# ELRS_Logic.net
KiCad netlist of a schematic drawn in Altium Designer
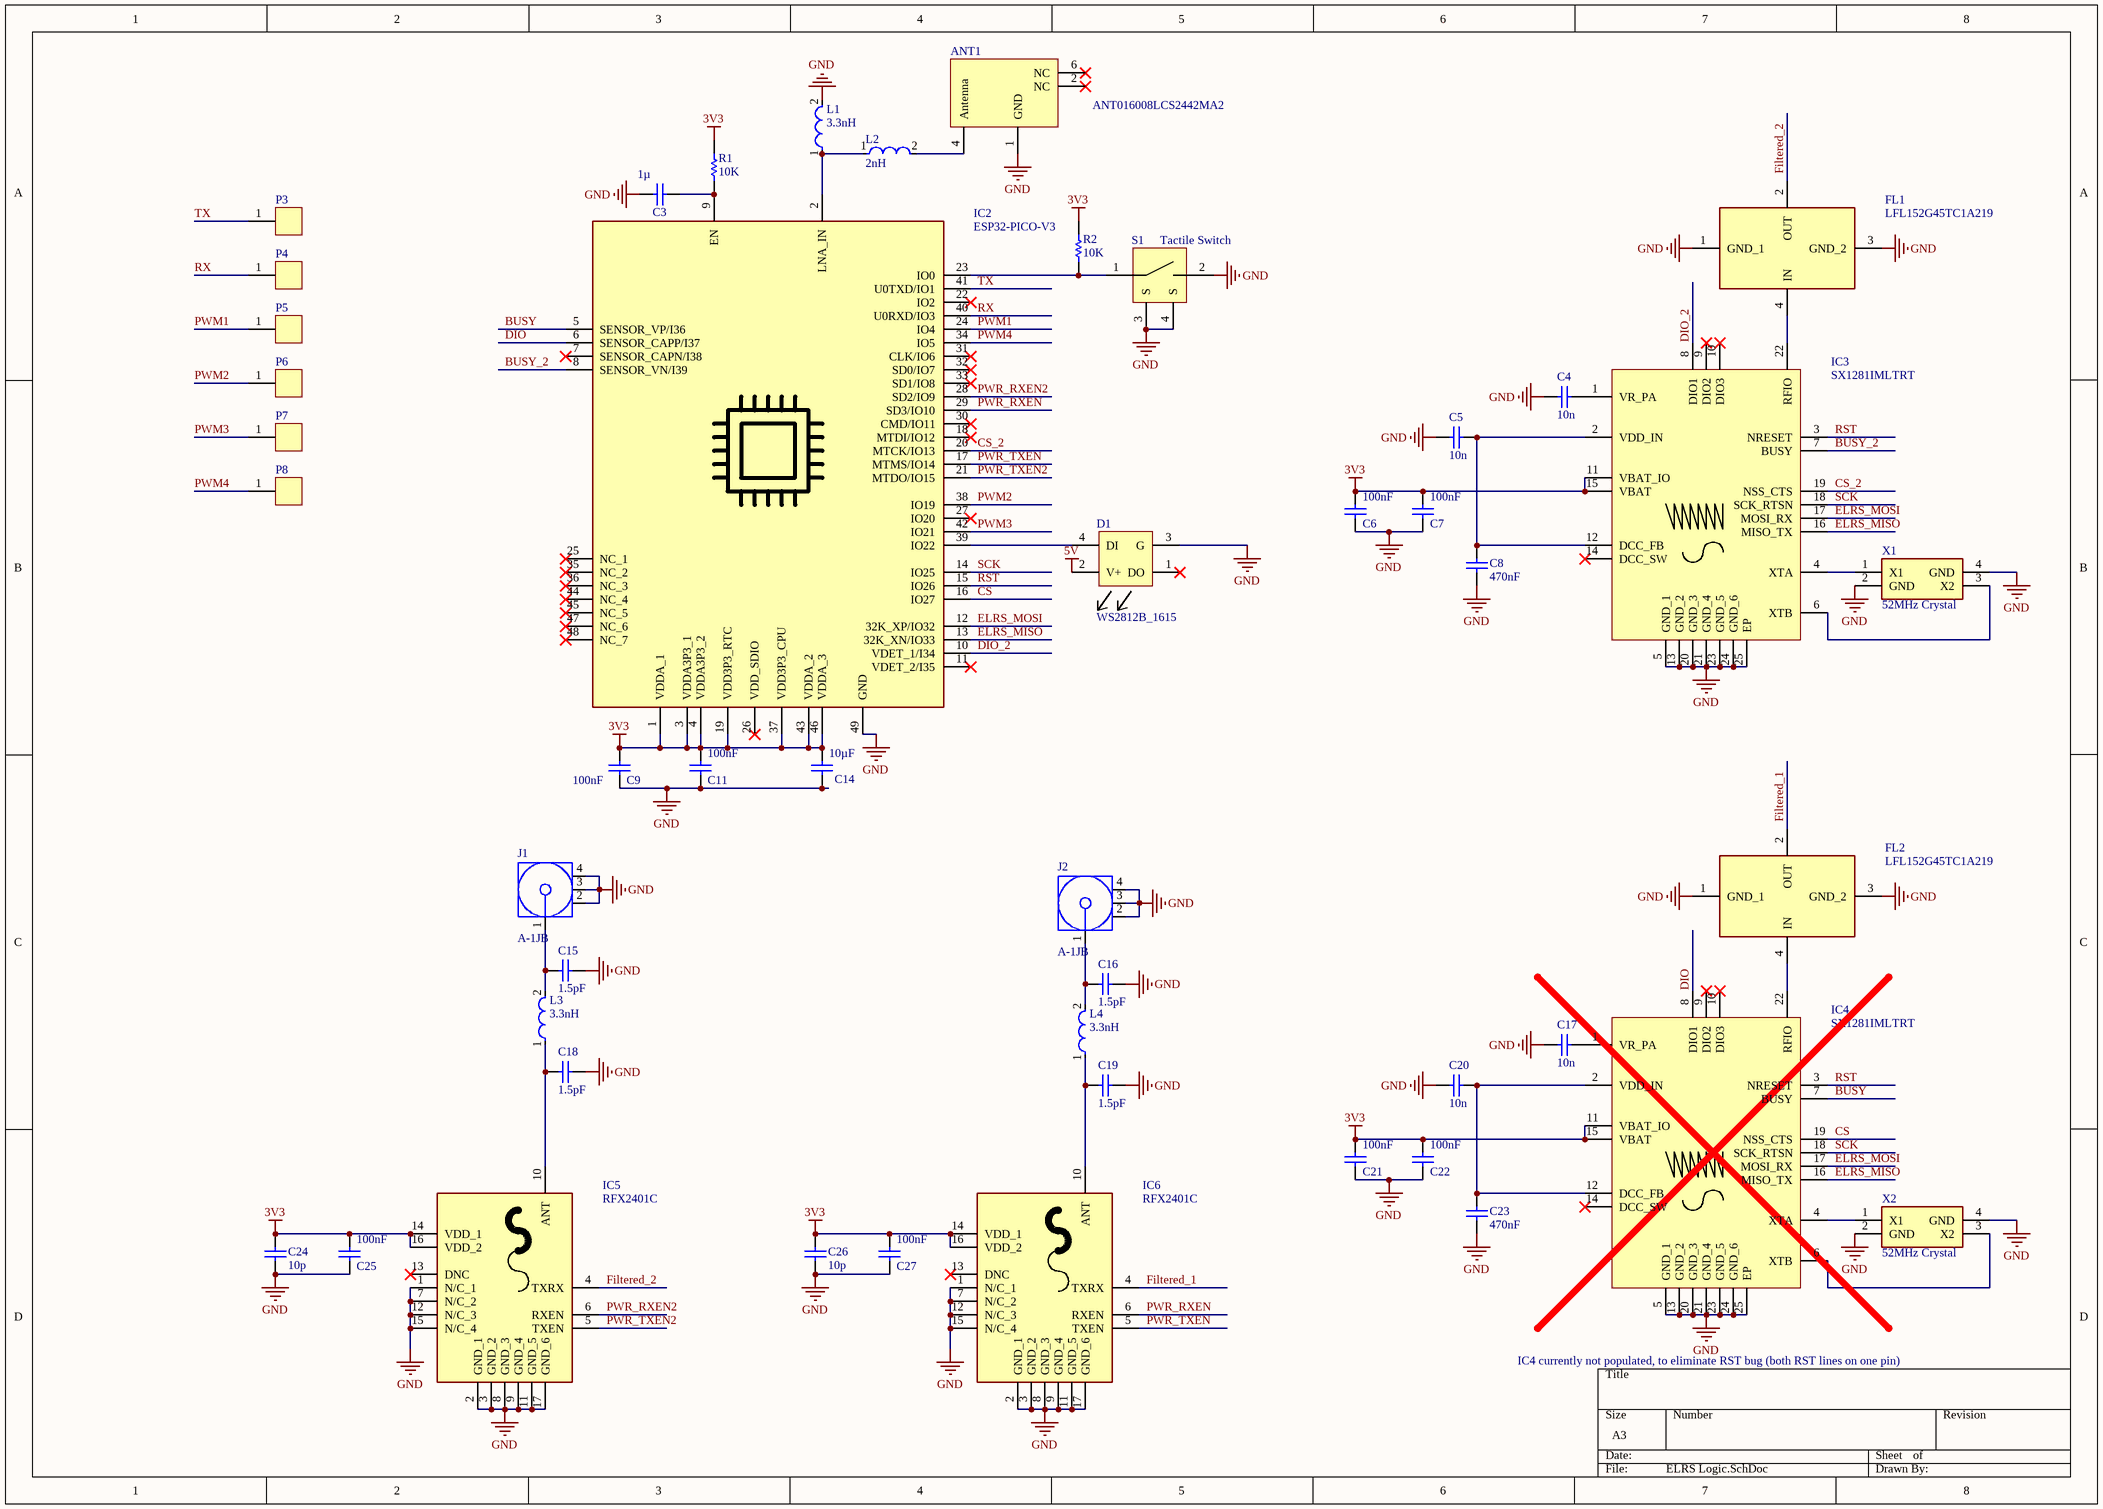
[diagram p0: ELRS Logic.SchDoc]

(export (version "E")
  (design (tool "Eeschema 10.0.6"))
  (components
    (comp (ref "ANT1")
      (value "ANT016008LCS2442MA2")
      (footprint "Custom Components:ANT016008LCS2442MA2")
      (description "Antenna")
      (fields (field (name "MOUSER PART NUMBER") "810-ANT168LCS2442MA2"))
      (libsource (lib "Custom Components") (part "ANT016008LCS2442MA2"))
    )
    (comp (ref "C3")
      (value "1µ")
      (footprint "WCAP-CSGP_0603_L1.6W0.8H0.8_Reflow")
      (description "WCAP-CSGP Multilayer Ceramic Chip Capacitor, General Purpose, size 0603, X7R, 100nF, 50VDC")
      (fields
        (field (name "MANUFACTURER PART NUMBER") "885012206095")
        (field (name "MANUFACTURER") "Wurth Elektronik")
      )
      (libsource (lib "Altium_WCAP-CSGP (rev22f)") (part "885012206095"))
    )
    (comp (ref "C4")
      (value "10n")
      (footprint "CAPC0603(1608)55_N")
      (description "Keramikvielschichtkondensator, SMD, Baureihe MC, ± 20%")
      (fields (field (name "MANUFACTURER") "Multicomp"))
      (libsource (lib "Standardbauteile") (part "Cap 10n"))
    )
    (comp (ref "C5")
      (value "10n")
      (footprint "CAPC0603(1608)55_N")
      (description "Keramikvielschichtkondensator, SMD, Baureihe MC, ± 20%")
      (fields (field (name "MANUFACTURER") "Multicomp"))
      (libsource (lib "Standardbauteile") (part "Cap 10n"))
    )
    (comp (ref "C6")
      (value "100nF")
      (footprint "WCAP-CSGP_0603_L1.6W0.8H0.8_Reflow")
      (description "WCAP-CSGP Multilayer Ceramic Chip Capacitor, General Purpose, size 0603, X7R, 100nF, 50VDC")
      (fields
        (field (name "MANUFACTURER PART NUMBER") "885012206095")
        (field (name "MANUFACTURER") "Wurth Elektronik")
      )
      (libsource (lib "Altium_WCAP-CSGP (rev22f)") (part "885012206095"))
    )
    (comp (ref "C7")
      (value "100nF")
      (footprint "WCAP-CSGP_0603_L1.6W0.8H0.8_Reflow")
      (description "WCAP-CSGP Multilayer Ceramic Chip Capacitor, General Purpose, size 0603, X7R, 100nF, 50VDC")
      (fields
        (field (name "MANUFACTURER PART NUMBER") "885012206095")
        (field (name "MANUFACTURER") "Wurth Elektronik")
      )
      (libsource (lib "Altium_WCAP-CSGP (rev22f)") (part "885012206095"))
    )
    (comp (ref "C8")
      (value "470nF")
      (footprint "0402 cap")
      (libsource (lib "Custom Components") (part "Capacitor 0402 100nF"))
    )
    (comp (ref "C9")
      (value "100nF")
      (footprint "WCAP-CSGP_0603_L1.6W0.8H0.8_Reflow")
      (description "WCAP-CSGP Multilayer Ceramic Chip Capacitor, General Purpose, size 0603, X7R, 100nF, 50VDC")
      (fields
        (field (name "MANUFACTURER PART NUMBER") "885012206095")
        (field (name "MANUFACTURER") "Wurth Elektronik")
      )
      (libsource (lib "Altium_WCAP-CSGP (rev22f)") (part "885012206095"))
    )
    (comp (ref "C11")
      (value "100nF")
      (footprint "WCAP-CSGP_0603_L1.6W0.8H0.8_Reflow")
      (description "WCAP-CSGP Multilayer Ceramic Chip Capacitor, General Purpose, size 0603, X7R, 100nF, 50VDC")
      (fields
        (field (name "MANUFACTURER PART NUMBER") "885012206095")
        (field (name "MANUFACTURER") "Wurth Elektronik")
      )
      (libsource (lib "Altium_WCAP-CSGP (rev22f)") (part "885012206095"))
    )
    (comp (ref "C14")
      (value "10µF")
      (footprint "WCAP-CSGP_0603_L1.6W0.8H0.8_Reflow")
      (description "WCAP-CSGP Multilayer Ceramic Chip Capacitor, General Purpose, size 0603, X5R, 10µF, 25VDC")
      (fields
        (field (name "MANUFACTURER PART NUMBER") "885012106031")
        (field (name "MANUFACTURER") "Wurth Elektronik")
      )
      (libsource (lib "Altium_WCAP-CSGP (rev22f)") (part "885012106031"))
    )
    (comp (ref "C15")
      (value "1.5pF")
      (footprint "0402 cap")
      (description "CL05C1R5BB5NNNC")
      (libsource (lib "Custom Components") (part "Capacitor 0402 100nF"))
    )
    (comp (ref "C16")
      (value "1.5pF")
      (footprint "0402 cap")
      (description "CL05C1R5BB5NNNC")
      (libsource (lib "Custom Components") (part "Capacitor 0402 100nF"))
    )
    (comp (ref "C17")
      (value "10n")
      (footprint "CAPC0603(1608)55_N")
      (description "Keramikvielschichtkondensator, SMD, Baureihe MC, ± 20%")
      (fields (field (name "MANUFACTURER") "Multicomp"))
      (libsource (lib "Standardbauteile") (part "Cap 10n"))
    )
    (comp (ref "C18")
      (value "1.5pF")
      (footprint "0402 cap")
      (description "CL05C1R5BB5NNNC")
      (libsource (lib "Custom Components") (part "Capacitor 0402 100nF"))
    )
    (comp (ref "C19")
      (value "1.5pF")
      (footprint "0402 cap")
      (description "CL05C1R5BB5NNNC")
      (libsource (lib "Custom Components") (part "Capacitor 0402 100nF"))
    )
    (comp (ref "C20")
      (value "10n")
      (footprint "CAPC0603(1608)55_N")
      (description "Keramikvielschichtkondensator, SMD, Baureihe MC, ± 20%")
      (fields (field (name "MANUFACTURER") "Multicomp"))
      (libsource (lib "Standardbauteile") (part "Cap 10n"))
    )
    (comp (ref "C21")
      (value "100nF")
      (footprint "WCAP-CSGP_0603_L1.6W0.8H0.8_Reflow")
      (description "WCAP-CSGP Multilayer Ceramic Chip Capacitor, General Purpose, size 0603, X7R, 100nF, 50VDC")
      (fields
        (field (name "MANUFACTURER PART NUMBER") "885012206095")
        (field (name "MANUFACTURER") "Wurth Elektronik")
      )
      (libsource (lib "Altium_WCAP-CSGP (rev22f)") (part "885012206095"))
    )
    (comp (ref "C22")
      (value "100nF")
      (footprint "WCAP-CSGP_0603_L1.6W0.8H0.8_Reflow")
      (description "WCAP-CSGP Multilayer Ceramic Chip Capacitor, General Purpose, size 0603, X7R, 100nF, 50VDC")
      (fields
        (field (name "MANUFACTURER PART NUMBER") "885012206095")
        (field (name "MANUFACTURER") "Wurth Elektronik")
      )
      (libsource (lib "Altium_WCAP-CSGP (rev22f)") (part "885012206095"))
    )
    (comp (ref "C23")
      (value "470nF")
      (footprint "0402 cap")
      (libsource (lib "Custom Components") (part "Capacitor 0402 100nF"))
    )
    (comp (ref "C24")
      (value "10p")
      (footprint "0402 cap")
      (libsource (lib "Custom Components") (part "Capacitor 0402 100nF"))
    )
    (comp (ref "C25")
      (value "100nF")
      (footprint "WCAP-CSGP_0603_L1.6W0.8H0.8_Reflow")
      (description "WCAP-CSGP Multilayer Ceramic Chip Capacitor, General Purpose, size 0603, X7R, 100nF, 50VDC")
      (fields
        (field (name "MANUFACTURER PART NUMBER") "885012206095")
        (field (name "MANUFACTURER") "Wurth Elektronik")
      )
      (libsource (lib "Altium_WCAP-CSGP (rev22f)") (part "885012206095"))
    )
    (comp (ref "C26")
      (value "10p")
      (footprint "0402 cap")
      (libsource (lib "Custom Components") (part "Capacitor 0402 100nF"))
    )
    (comp (ref "C27")
      (value "100nF")
      (footprint "WCAP-CSGP_0603_L1.6W0.8H0.8_Reflow")
      (description "WCAP-CSGP Multilayer Ceramic Chip Capacitor, General Purpose, size 0603, X7R, 100nF, 50VDC")
      (fields
        (field (name "MANUFACTURER PART NUMBER") "885012206095")
        (field (name "MANUFACTURER") "Wurth Elektronik")
      )
      (libsource (lib "Altium_WCAP-CSGP (rev22f)") (part "885012206095"))
    )
    (comp (ref "D1")
      (value "WS2812B_1615")
      (footprint "WS2812B_1615")
      (description "XINGLIGHT XL-1615RGBC-WS2812B")
      (libsource (lib "Custom Components") (part "WS2812B_1615"))
    )
    (comp (ref "FL1")
      (value "LFL152G45TC1A219")
      (footprint "LFL152G45TC1A219")
      (description "Filter")
      (fields (field (name "MOUSER PART NUMBER") "81-LFL152G45TC1A219"))
      (libsource (lib "Custom Components") (part "LFL152G45TC1A219"))
    )
    (comp (ref "FL2")
      (value "LFL152G45TC1A219")
      (footprint "LFL152G45TC1A219")
      (description "Filter")
      (fields (field (name "MOUSER PART NUMBER") "81-LFL152G45TC1A219"))
      (libsource (lib "Custom Components") (part "LFL152G45TC1A219"))
    )
    (comp (ref "IC2")
      (value "ESP32-PICO-V3")
      (footprint "Custom Components:ESP32PICOV3")
      (description "Integrated Circuit")
      (fields (field (name "MOUSER PART NUMBER") "356-ESP32-PICO-V3"))
      (libsource (lib "Custom Components") (part "ESP32-PICO-V3"))
    )
    (comp (ref "IC3")
      (value "SX1281IMLTRT")
      (footprint "Custom Components:QFN50P400X400X100-25N-D")
      (description "Integrated Circuit")
      (fields (field (name "MOUSER PART NUMBER") "947-SX1281IMLTRT"))
      (libsource (lib "Custom Components") (part "SX1281IMLTRT"))
    )
    (comp (ref "IC4")
      (value "SX1281IMLTRT")
      (footprint "Custom Components:QFN50P400X400X100-25N-D")
      (description "Integrated Circuit")
      (fields (field (name "MOUSER PART NUMBER") "947-SX1281IMLTRT"))
      (libsource (lib "Custom Components") (part "SX1281IMLTRT"))
    )
    (comp (ref "IC5")
      (value "RFX2401C")
      (footprint "Custom Components:QFN50P300X300X60-17N-D")
      (description "Integrated Circuit")
      (fields (field (name "MOUSER PART NUMBER") "477-RFX2401C"))
      (libsource (lib "Custom Components") (part "RFX2401C"))
    )
    (comp (ref "IC6")
      (value "RFX2401C")
      (footprint "Custom Components:QFN50P300X300X60-17N-D")
      (description "Integrated Circuit")
      (fields (field (name "MOUSER PART NUMBER") "477-RFX2401C"))
      (libsource (lib "Custom Components") (part "RFX2401C"))
    )
    (comp (ref "J1")
      (value "A-1JB")
      (footprint "AMPH-A-1JB_V")
      (description "AMC PCB Jack, 0 to 60 GHz, 60 V, -40 to 90 degC, 4-Pin SMD, RoHS, Tape and Reel")
      (fields (field (name "TOLERANCE") "10%"))
      (libsource (lib "Altium Content Vault") (part "CN-S-3F-RF4"))
    )
    (comp (ref "J2")
      (value "A-1JB")
      (footprint "AMPH-A-1JB_V")
      (description "AMC PCB Jack, 0 to 60 GHz, 60 V, -40 to 90 degC, 4-Pin SMD, RoHS, Tape and Reel")
      (fields (field (name "TOLERANCE") "10%"))
      (libsource (lib "Altium Content Vault") (part "CN-S-3F-RF4"))
    )
    (comp (ref "L1")
      (value "3.3nH")
      (footprint "FP-LQW15AN_00-W0_6-0_1-MFG")
      (description "MLG1005S3N3BT000")
      (libsource (lib "Altium Content Vault") (part "725321dda6339637d4d059423bc1c3c"))
    )
    (comp (ref "L2")
      (value "2nH")
      (footprint "FP-LQW15AN_00-W0_6-0_1-MFG")
      (description "MLG1005S3N3BT000")
      (libsource (lib "Altium Content Vault") (part "725321dda6339637d4d059423bc1c3c"))
    )
    (comp (ref "L3")
      (value "3.3nH")
      (footprint "FP-LQW15AN_00-W0_6-0_1-MFG")
      (description "MLG1005S3N3BT000")
      (libsource (lib "Altium Content Vault") (part "725321dda6339637d4d059423bc1c3c"))
    )
    (comp (ref "L4")
      (value "3.3nH")
      (footprint "FP-LQW15AN_00-W0_6-0_1-MFG")
      (description "MLG1005S3N3BT000")
      (libsource (lib "Altium Content Vault") (part "725321dda6339637d4d059423bc1c3c"))
    )
    (comp (ref "P3")
      (value "solder pad rounded single sided")
      (footprint "solder pad single sided rounded")
      (libsource (lib "Custom Components") (part "solder pad rounded single sided"))
    )
    (comp (ref "P4")
      (value "solder pad rounded single sided")
      (footprint "solder pad single sided rounded")
      (libsource (lib "Custom Components") (part "solder pad rounded single sided"))
    )
    (comp (ref "P5")
      (value "solder pad rounded single sided")
      (footprint "solder pad single sided rounded")
      (libsource (lib "Custom Components") (part "solder pad rounded single sided"))
    )
    (comp (ref "P6")
      (value "solder pad rounded single sided")
      (footprint "solder pad single sided rounded")
      (libsource (lib "Custom Components") (part "solder pad rounded single sided"))
    )
    (comp (ref "P7")
      (value "solder pad rounded single sided")
      (footprint "solder pad single sided rounded")
      (libsource (lib "Custom Components") (part "solder pad rounded single sided"))
    )
    (comp (ref "P8")
      (value "solder pad rounded single sided")
      (footprint "solder pad single sided rounded")
      (libsource (lib "Custom Components") (part "solder pad rounded single sided"))
    )
    (comp (ref "R1")
      (value "10K")
      (footprint "RESC0603(1608)_N")
      (description "Chipwiderstand, SMD, Baureihe MC, 1%")
      (fields (field (name "MANUFACTURER") "Multicomp"))
      (libsource (lib "Standardbauteile") (part "Res 1K"))
    )
    (comp (ref "R2")
      (value "10K")
      (footprint "RESC0603(1608)_N")
      (description "Chipwiderstand, SMD, Baureihe MC, 1%")
      (fields (field (name "MANUFACTURER") "Multicomp"))
      (libsource (lib "Standardbauteile") (part "Res 10K"))
    )
    (comp (ref "S1")
      (value "Tactile Switch")
      (footprint "Tactile Switch")
      (libsource (lib "Custom Components") (part "Tactile Switch"))
    )
    (comp (ref "X1")
      (value "52MHz Crystal")
      (footprint "2016 Crystal")
      (description "HCI XC21M4-52.000-F10NNHPL")
      (libsource (lib "Custom Components") (part "HCI XC21M4-52.000"))
    )
    (comp (ref "X2")
      (value "52MHz Crystal")
      (footprint "2016 Crystal")
      (description "HCI XC21M4-52.000-F10NNHPL")
      (libsource (lib "Custom Components") (part "HCI XC21M4-52.000"))
    )
  )
  (nets
    (net (code "1") (name "/BUSY") (class "Default")
      (node (ref "IC2") (pin "5") (pinfunction "SENSOR_VP/I36_5") (pintype "passive"))
      (node (ref "IC4") (pin "7") (pinfunction "BUSY_7") (pintype "passive"))
    )
    (net (code "2") (name "/BUSY_2") (class "Default")
      (node (ref "IC2") (pin "8") (pinfunction "SENSOR_VN/I39_8") (pintype "passive"))
      (node (ref "IC3") (pin "7") (pinfunction "BUSY_7") (pintype "passive"))
    )
    (net (code "3") (name "/CS") (class "Default")
      (node (ref "IC2") (pin "16") (pinfunction "IO27_16") (pintype "passive"))
      (node (ref "IC4") (pin "19") (pinfunction "NSS_CTS_19") (pintype "passive"))
    )
    (net (code "4") (name "/CS_2") (class "Default")
      (node (ref "IC2") (pin "20") (pinfunction "MTCK/IO13_20") (pintype "passive"))
      (node (ref "IC3") (pin "19") (pinfunction "NSS_CTS_19") (pintype "passive"))
    )
    (net (code "5") (name "/DIO") (class "Default")
      (node (ref "IC2") (pin "6") (pinfunction "SENSOR_CAPP/I37_6") (pintype "passive"))
      (node (ref "IC4") (pin "8") (pinfunction "DIO1_8") (pintype "passive"))
    )
    (net (code "6") (name "/DIO_2") (class "Default")
      (node (ref "IC2") (pin "10") (pinfunction "VDET_1/I34_10") (pintype "passive"))
      (node (ref "IC3") (pin "8") (pinfunction "DIO1_8") (pintype "passive"))
    )
    (net (code "7") (name "/ELRS_MISO") (class "Default")
      (node (ref "IC2") (pin "13") (pinfunction "32K_XN/IO33_13") (pintype "passive"))
      (node (ref "IC3") (pin "16") (pinfunction "MISO_TX_16") (pintype "passive"))
      (node (ref "IC4") (pin "16") (pinfunction "MISO_TX_16") (pintype "passive"))
    )
    (net (code "8") (name "/ELRS_MOSI") (class "Default")
      (node (ref "IC2") (pin "12") (pinfunction "32K_XP/IO32_12") (pintype "passive"))
      (node (ref "IC3") (pin "17") (pinfunction "MOSI_RX_17") (pintype "passive"))
      (node (ref "IC4") (pin "17") (pinfunction "MOSI_RX_17") (pintype "passive"))
    )
    (net (code "9") (name "/Filtered_1") (class "Default")
      (node (ref "FL2") (pin "2") (pinfunction "OUT_2") (pintype "passive"))
      (node (ref "IC6") (pin "4") (pinfunction "TXRX_4") (pintype "passive"))
    )
    (net (code "10") (name "/Filtered_2") (class "Default")
      (node (ref "FL1") (pin "2") (pinfunction "OUT_2") (pintype "passive"))
      (node (ref "IC5") (pin "4") (pinfunction "TXRX_4") (pintype "passive"))
    )
    (net (code "11") (name "/PWM1") (class "Default")
      (node (ref "IC2") (pin "24") (pinfunction "IO4_24") (pintype "passive"))
      (node (ref "P5") (pin "1") (pinfunction "upper_1") (pintype "passive"))
    )
    (net (code "12") (name "/PWM2") (class "Default")
      (node (ref "IC2") (pin "38") (pinfunction "IO19_38") (pintype "passive"))
      (node (ref "P6") (pin "1") (pinfunction "upper_1") (pintype "passive"))
    )
    (net (code "13") (name "/PWM3") (class "Default")
      (node (ref "IC2") (pin "42") (pinfunction "IO21_42") (pintype "passive"))
      (node (ref "P7") (pin "1") (pinfunction "upper_1") (pintype "passive"))
    )
    (net (code "14") (name "/PWM4") (class "Default")
      (node (ref "IC2") (pin "34") (pinfunction "IO5_34") (pintype "passive"))
      (node (ref "P8") (pin "1") (pinfunction "upper_1") (pintype "passive"))
    )
    (net (code "15") (name "/PWR_RXEN") (class "Default")
      (node (ref "IC2") (pin "29") (pinfunction "SD3/IO10_29") (pintype "passive"))
      (node (ref "IC6") (pin "6") (pinfunction "RXEN_6") (pintype "passive"))
    )
    (net (code "16") (name "/PWR_RXEN2") (class "Default")
      (node (ref "IC2") (pin "28") (pinfunction "SD2/IO9_28") (pintype "passive"))
      (node (ref "IC5") (pin "6") (pinfunction "RXEN_6") (pintype "passive"))
    )
    (net (code "17") (name "/PWR_TXEN") (class "Default")
      (node (ref "IC2") (pin "17") (pinfunction "MTMS/IO14_17") (pintype "passive"))
      (node (ref "IC6") (pin "5") (pinfunction "TXEN_5") (pintype "passive"))
    )
    (net (code "18") (name "/PWR_TXEN2") (class "Default")
      (node (ref "IC2") (pin "21") (pinfunction "MTDO/IO15_21") (pintype "passive"))
      (node (ref "IC5") (pin "5") (pinfunction "TXEN_5") (pintype "passive"))
    )
    (net (code "19") (name "/RST") (class "Default")
      (node (ref "IC2") (pin "15") (pinfunction "IO26_15") (pintype "passive"))
      (node (ref "IC3") (pin "3") (pinfunction "NRESET_3") (pintype "passive"))
      (node (ref "IC4") (pin "3") (pinfunction "NRESET_3") (pintype "passive"))
    )
    (net (code "20") (name "/RX") (class "Default")
      (node (ref "IC2") (pin "40") (pinfunction "U0RXD/IO3_40") (pintype "passive"))
      (node (ref "P4") (pin "1") (pinfunction "upper_1") (pintype "passive"))
    )
    (net (code "21") (name "/SCK") (class "Default")
      (node (ref "IC2") (pin "14") (pinfunction "IO25_14") (pintype "passive"))
      (node (ref "IC3") (pin "18") (pinfunction "SCK_RTSN_18") (pintype "passive"))
      (node (ref "IC4") (pin "18") (pinfunction "SCK_RTSN_18") (pintype "passive"))
    )
    (net (code "22") (name "/TX") (class "Default")
      (node (ref "IC2") (pin "41") (pinfunction "U0TXD/IO1_41") (pintype "passive"))
      (node (ref "P3") (pin "1") (pinfunction "upper_1") (pintype "passive"))
    )
    (net (code "23") (name "3V3") (class "Default")
      (node (ref "C11") (pin "2") (pinfunction "2_2") (pintype "passive"))
      (node (ref "C14") (pin "2") (pinfunction "2_2") (pintype "passive"))
      (node (ref "C21") (pin "2") (pinfunction "2_2") (pintype "passive"))
      (node (ref "C22") (pin "2") (pinfunction "2_2") (pintype "passive"))
      (node (ref "C24") (pin "2") (pinfunction "2_2") (pintype "passive"))
      (node (ref "C25") (pin "2") (pinfunction "2_2") (pintype "passive"))
      (node (ref "C26") (pin "2") (pinfunction "2_2") (pintype "passive"))
      (node (ref "C27") (pin "2") (pinfunction "2_2") (pintype "passive"))
      (node (ref "C6") (pin "2") (pinfunction "2_2") (pintype "passive"))
      (node (ref "C7") (pin "2") (pinfunction "2_2") (pintype "passive"))
      (node (ref "C9") (pin "2") (pinfunction "2_2") (pintype "passive"))
      (node (ref "IC2") (pin "1") (pinfunction "VDDA_1_1") (pintype "passive"))
      (node (ref "IC2") (pin "19") (pinfunction "VDD3P3_RTC_19") (pintype "passive"))
      (node (ref "IC2") (pin "3") (pinfunction "VDDA3P3_1_3") (pintype "passive"))
      (node (ref "IC2") (pin "37") (pinfunction "VDD3P3_CPU_37") (pintype "passive"))
      (node (ref "IC2") (pin "4") (pinfunction "VDDA3P3_2_4") (pintype "passive"))
      (node (ref "IC2") (pin "43") (pinfunction "VDDA_2_43") (pintype "passive"))
      (node (ref "IC2") (pin "46") (pinfunction "VDDA_3_46") (pintype "passive"))
      (node (ref "IC3") (pin "11") (pinfunction "VBAT_IO_11") (pintype "passive"))
      (node (ref "IC3") (pin "15") (pinfunction "VBAT_15") (pintype "passive"))
      (node (ref "IC4") (pin "11") (pinfunction "VBAT_IO_11") (pintype "passive"))
      (node (ref "IC4") (pin "15") (pinfunction "VBAT_15") (pintype "passive"))
      (node (ref "IC5") (pin "14") (pinfunction "VDD_1_14") (pintype "passive"))
      (node (ref "IC5") (pin "16") (pinfunction "VDD_2_16") (pintype "passive"))
      (node (ref "IC6") (pin "14") (pinfunction "VDD_1_14") (pintype "passive"))
      (node (ref "IC6") (pin "16") (pinfunction "VDD_2_16") (pintype "passive"))
      (node (ref "R1") (pin "2") (pinfunction "2_2") (pintype "passive"))
      (node (ref "R2") (pin "2") (pinfunction "2_2") (pintype "passive"))
    )
    (net (code "24") (name "5V") (class "Default")
      (node (ref "D1") (pin "2") (pinfunction "V+_2") (pintype "passive"))
    )
    (net (code "25") (name "GND") (class "Default")
      (node (ref "ANT1") (pin "1") (pinfunction "GND_1") (pintype "passive"))
      (node (ref "C11") (pin "1") (pinfunction "1_1") (pintype "passive"))
      (node (ref "C14") (pin "1") (pinfunction "1_1") (pintype "passive"))
      (node (ref "C15") (pin "2") (pinfunction "2_2") (pintype "passive"))
      (node (ref "C16") (pin "2") (pinfunction "2_2") (pintype "passive"))
      (node (ref "C17") (pin "1") (pinfunction "1_1") (pintype "passive"))
      (node (ref "C18") (pin "2") (pinfunction "2_2") (pintype "passive"))
      (node (ref "C19") (pin "2") (pinfunction "2_2") (pintype "passive"))
      (node (ref "C20") (pin "1") (pinfunction "1_1") (pintype "passive"))
      (node (ref "C21") (pin "1") (pinfunction "1_1") (pintype "passive"))
      (node (ref "C22") (pin "1") (pinfunction "1_1") (pintype "passive"))
      (node (ref "C23") (pin "1") (pinfunction "1_1") (pintype "passive"))
      (node (ref "C24") (pin "1") (pinfunction "1_1") (pintype "passive"))
      (node (ref "C25") (pin "1") (pinfunction "1_1") (pintype "passive"))
      (node (ref "C26") (pin "1") (pinfunction "1_1") (pintype "passive"))
      (node (ref "C27") (pin "1") (pinfunction "1_1") (pintype "passive"))
      (node (ref "C3") (pin "2") (pinfunction "2_2") (pintype "passive"))
      (node (ref "C4") (pin "1") (pinfunction "1_1") (pintype "passive"))
      (node (ref "C5") (pin "1") (pinfunction "1_1") (pintype "passive"))
      (node (ref "C6") (pin "1") (pinfunction "1_1") (pintype "passive"))
      (node (ref "C7") (pin "1") (pinfunction "1_1") (pintype "passive"))
      (node (ref "C8") (pin "1") (pinfunction "1_1") (pintype "passive"))
      (node (ref "C9") (pin "1") (pinfunction "1_1") (pintype "passive"))
      (node (ref "D1") (pin "3") (pinfunction "G_3") (pintype "passive"))
      (node (ref "FL1") (pin "1") (pinfunction "GND_1_1") (pintype "passive"))
      (node (ref "FL1") (pin "3") (pinfunction "GND_2_3") (pintype "passive"))
      (node (ref "FL2") (pin "1") (pinfunction "GND_1_1") (pintype "passive"))
      (node (ref "FL2") (pin "3") (pinfunction "GND_2_3") (pintype "passive"))
      (node (ref "IC2") (pin "49") (pinfunction "GND_49") (pintype "passive"))
      (node (ref "IC3") (pin "13") (pinfunction "GND_2_13") (pintype "passive"))
      (node (ref "IC3") (pin "20") (pinfunction "GND_3_20") (pintype "passive"))
      (node (ref "IC3") (pin "21") (pinfunction "GND_4_21") (pintype "passive"))
      (node (ref "IC3") (pin "23") (pinfunction "GND_5_23") (pintype "passive"))
      (node (ref "IC3") (pin "24") (pinfunction "GND_6_24") (pintype "passive"))
      (node (ref "IC3") (pin "25") (pinfunction "EP_25") (pintype "passive"))
      (node (ref "IC3") (pin "5") (pinfunction "GND_1_5") (pintype "passive"))
      (node (ref "IC4") (pin "13") (pinfunction "GND_2_13") (pintype "passive"))
      (node (ref "IC4") (pin "20") (pinfunction "GND_3_20") (pintype "passive"))
      (node (ref "IC4") (pin "21") (pinfunction "GND_4_21") (pintype "passive"))
      (node (ref "IC4") (pin "23") (pinfunction "GND_5_23") (pintype "passive"))
      (node (ref "IC4") (pin "24") (pinfunction "GND_6_24") (pintype "passive"))
      (node (ref "IC4") (pin "25") (pinfunction "EP_25") (pintype "passive"))
      (node (ref "IC4") (pin "5") (pinfunction "GND_1_5") (pintype "passive"))
      (node (ref "IC5") (pin "1") (pinfunction "N/C_1_1") (pintype "passive"))
      (node (ref "IC5") (pin "11") (pinfunction "GND_5_11") (pintype "passive"))
      (node (ref "IC5") (pin "12") (pinfunction "N/C_3_12") (pintype "passive"))
      (node (ref "IC5") (pin "15") (pinfunction "N/C_4_15") (pintype "passive"))
      (node (ref "IC5") (pin "17") (pinfunction "GND_6_17") (pintype "passive"))
      (node (ref "IC5") (pin "2") (pinfunction "GND_1_2") (pintype "passive"))
      (node (ref "IC5") (pin "3") (pinfunction "GND_2_3") (pintype "passive"))
      (node (ref "IC5") (pin "7") (pinfunction "N/C_2_7") (pintype "passive"))
      (node (ref "IC5") (pin "8") (pinfunction "GND_3_8") (pintype "passive"))
      (node (ref "IC5") (pin "9") (pinfunction "GND_4_9") (pintype "passive"))
      (node (ref "IC6") (pin "1") (pinfunction "N/C_1_1") (pintype "passive"))
      (node (ref "IC6") (pin "11") (pinfunction "GND_5_11") (pintype "passive"))
      (node (ref "IC6") (pin "12") (pinfunction "N/C_3_12") (pintype "passive"))
      (node (ref "IC6") (pin "15") (pinfunction "N/C_4_15") (pintype "passive"))
      (node (ref "IC6") (pin "17") (pinfunction "GND_6_17") (pintype "passive"))
      (node (ref "IC6") (pin "2") (pinfunction "GND_1_2") (pintype "passive"))
      (node (ref "IC6") (pin "3") (pinfunction "GND_2_3") (pintype "passive"))
      (node (ref "IC6") (pin "7") (pinfunction "N/C_2_7") (pintype "passive"))
      (node (ref "IC6") (pin "8") (pinfunction "GND_3_8") (pintype "passive"))
      (node (ref "IC6") (pin "9") (pinfunction "GND_4_9") (pintype "passive"))
      (node (ref "J1") (pin "2") (pinfunction "2_2") (pintype "passive"))
      (node (ref "J1") (pin "3") (pinfunction "3_3") (pintype "passive"))
      (node (ref "J1") (pin "4") (pinfunction "4_4") (pintype "passive"))
      (node (ref "J2") (pin "2") (pinfunction "2_2") (pintype "passive"))
      (node (ref "J2") (pin "3") (pinfunction "3_3") (pintype "passive"))
      (node (ref "J2") (pin "4") (pinfunction "4_4") (pintype "passive"))
      (node (ref "L1") (pin "2") (pinfunction "2_2") (pintype "passive"))
      (node (ref "S1") (pin "2") (pintype "passive"))
      (node (ref "S1") (pin "3") (pinfunction "S_3") (pintype "passive"))
      (node (ref "S1") (pin "4") (pinfunction "S_4") (pintype "passive"))
      (node (ref "X1") (pin "2") (pinfunction "GND_2") (pintype "passive"))
      (node (ref "X1") (pin "4") (pinfunction "GND_4") (pintype "passive"))
      (node (ref "X2") (pin "2") (pinfunction "GND_2") (pintype "passive"))
      (node (ref "X2") (pin "4") (pinfunction "GND_4") (pintype "passive"))
    )
    (net (code "26") (name "Net-(ANT1-Antenna)") (class "Default")
      (node (ref "ANT1") (pin "4") (pinfunction "Antenna_4") (pintype "passive"))
      (node (ref "L2") (pin "2") (pinfunction "2_2") (pintype "passive"))
    )
    (net (code "27") (name "Net-(C15-Pad1)") (class "Default")
      (node (ref "C15") (pin "1") (pinfunction "1_1") (pintype "passive"))
      (node (ref "J1") (pin "1") (pinfunction "1_1") (pintype "passive"))
      (node (ref "L3") (pin "2") (pinfunction "2_2") (pintype "passive"))
    )
    (net (code "28") (name "Net-(C16-Pad1)") (class "Default")
      (node (ref "C16") (pin "1") (pinfunction "1_1") (pintype "passive"))
      (node (ref "J2") (pin "1") (pinfunction "1_1") (pintype "passive"))
      (node (ref "L4") (pin "2") (pinfunction "2_2") (pintype "passive"))
    )
    (net (code "29") (name "Net-(D1-DI)") (class "Default")
      (node (ref "D1") (pin "4") (pinfunction "DI_4") (pintype "passive"))
      (node (ref "IC2") (pin "39") (pinfunction "IO22_39") (pintype "passive"))
    )
    (net (code "30") (name "Net-(FL1-IN)") (class "Default")
      (node (ref "FL1") (pin "4") (pinfunction "IN_4") (pintype "passive"))
      (node (ref "IC3") (pin "22") (pinfunction "RFIO_22") (pintype "passive"))
    )
    (net (code "31") (name "Net-(FL2-IN)") (class "Default")
      (node (ref "FL2") (pin "4") (pinfunction "IN_4") (pintype "passive"))
      (node (ref "IC4") (pin "22") (pinfunction "RFIO_22") (pintype "passive"))
    )
    (net (code "32") (name "Net-(IC2-EN)") (class "Default")
      (node (ref "C3") (pin "1") (pinfunction "1_1") (pintype "passive"))
      (node (ref "IC2") (pin "9") (pinfunction "EN_9") (pintype "passive"))
      (node (ref "R1") (pin "1") (pinfunction "1_1") (pintype "passive"))
    )
    (net (code "33") (name "Net-(IC2-IO0)") (class "Default")
      (node (ref "IC2") (pin "23") (pinfunction "IO0_23") (pintype "passive"))
      (node (ref "R2") (pin "1") (pinfunction "1_1") (pintype "passive"))
      (node (ref "S1") (pin "1") (pintype "passive"))
    )
    (net (code "34") (name "Net-(IC2-LNA_IN)") (class "Default")
      (node (ref "IC2") (pin "2") (pinfunction "LNA_IN_2") (pintype "passive"))
      (node (ref "L1") (pin "1") (pinfunction "1_1") (pintype "passive"))
      (node (ref "L2") (pin "1") (pinfunction "1_1") (pintype "passive"))
    )
    (net (code "35") (name "Net-(IC3-DCC_FB)") (class "Default")
      (node (ref "C5") (pin "2") (pinfunction "2_2") (pintype "passive"))
      (node (ref "C8") (pin "2") (pinfunction "2_2") (pintype "passive"))
      (node (ref "IC3") (pin "12") (pinfunction "DCC_FB_12") (pintype "passive"))
      (node (ref "IC3") (pin "2") (pinfunction "VDD_IN_2") (pintype "passive"))
    )
    (net (code "36") (name "Net-(IC3-VR_PA)") (class "Default")
      (node (ref "C4") (pin "2") (pinfunction "2_2") (pintype "passive"))
      (node (ref "IC3") (pin "1") (pinfunction "VR_PA_1") (pintype "passive"))
    )
    (net (code "37") (name "Net-(IC3-XTA)") (class "Default")
      (node (ref "IC3") (pin "4") (pinfunction "XTA_4") (pintype "passive"))
      (node (ref "X1") (pin "1") (pinfunction "X1_1") (pintype "passive"))
    )
    (net (code "38") (name "Net-(IC3-XTB)") (class "Default")
      (node (ref "IC3") (pin "6") (pinfunction "XTB_6") (pintype "passive"))
      (node (ref "X1") (pin "3") (pinfunction "X2_3") (pintype "passive"))
    )
    (net (code "39") (name "Net-(IC4-DCC_FB)") (class "Default")
      (node (ref "C20") (pin "2") (pinfunction "2_2") (pintype "passive"))
      (node (ref "C23") (pin "2") (pinfunction "2_2") (pintype "passive"))
      (node (ref "IC4") (pin "12") (pinfunction "DCC_FB_12") (pintype "passive"))
      (node (ref "IC4") (pin "2") (pinfunction "VDD_IN_2") (pintype "passive"))
    )
    (net (code "40") (name "Net-(IC4-VR_PA)") (class "Default")
      (node (ref "C17") (pin "2") (pinfunction "2_2") (pintype "passive"))
      (node (ref "IC4") (pin "1") (pinfunction "VR_PA_1") (pintype "passive"))
    )
    (net (code "41") (name "Net-(IC4-XTA)") (class "Default")
      (node (ref "IC4") (pin "4") (pinfunction "XTA_4") (pintype "passive"))
      (node (ref "X2") (pin "1") (pinfunction "X1_1") (pintype "passive"))
    )
    (net (code "42") (name "Net-(IC4-XTB)") (class "Default")
      (node (ref "IC4") (pin "6") (pinfunction "XTB_6") (pintype "passive"))
      (node (ref "X2") (pin "3") (pinfunction "X2_3") (pintype "passive"))
    )
    (net (code "43") (name "Net-(IC5-ANT)") (class "Default")
      (node (ref "C18") (pin "1") (pinfunction "1_1") (pintype "passive"))
      (node (ref "IC5") (pin "10") (pinfunction "ANT_10") (pintype "passive"))
      (node (ref "L3") (pin "1") (pinfunction "1_1") (pintype "passive"))
    )
    (net (code "44") (name "Net-(IC6-ANT)") (class "Default")
      (node (ref "C19") (pin "1") (pinfunction "1_1") (pintype "passive"))
      (node (ref "IC6") (pin "10") (pinfunction "ANT_10") (pintype "passive"))
      (node (ref "L4") (pin "1") (pinfunction "1_1") (pintype "passive"))
    )
    (net (code "45") (name "unconnected-(ANT1-NC-Pad2)") (class "Default")
      (node (ref "ANT1") (pin "2") (pinfunction "NC_2") (pintype "passive+no_connect"))
    )
    (net (code "46") (name "unconnected-(ANT1-NC-Pad6)") (class "Default")
      (node (ref "ANT1") (pin "6") (pinfunction "NC_6") (pintype "passive+no_connect"))
    )
    (net (code "47") (name "unconnected-(D1-DO-Pad1)") (class "Default")
      (node (ref "D1") (pin "1") (pinfunction "DO_1") (pintype "passive+no_connect"))
    )
    (net (code "48") (name "unconnected-(IC2-CLK{slash}IO6-Pad31)") (class "Default")
      (node (ref "IC2") (pin "31") (pinfunction "CLK/IO6_31") (pintype "passive+no_connect"))
    )
    (net (code "49") (name "unconnected-(IC2-CMD{slash}IO11-Pad30)") (class "Default")
      (node (ref "IC2") (pin "30") (pinfunction "CMD/IO11_30") (pintype "passive+no_connect"))
    )
    (net (code "50") (name "unconnected-(IC2-IO2-Pad22)") (class "Default")
      (node (ref "IC2") (pin "22") (pinfunction "IO2_22") (pintype "passive+no_connect"))
    )
    (net (code "51") (name "unconnected-(IC2-IO20-Pad27)") (class "Default")
      (node (ref "IC2") (pin "27") (pinfunction "IO20_27") (pintype "passive+no_connect"))
    )
    (net (code "52") (name "unconnected-(IC2-MTDI{slash}IO12-Pad18)") (class "Default")
      (node (ref "IC2") (pin "18") (pinfunction "MTDI/IO12_18") (pintype "passive+no_connect"))
    )
    (net (code "53") (name "unconnected-(IC2-NC_1-Pad25)") (class "Default")
      (node (ref "IC2") (pin "25") (pinfunction "NC_1_25") (pintype "passive+no_connect"))
    )
    (net (code "54") (name "unconnected-(IC2-NC_2-Pad35)") (class "Default")
      (node (ref "IC2") (pin "35") (pinfunction "NC_2_35") (pintype "passive+no_connect"))
    )
    (net (code "55") (name "unconnected-(IC2-NC_3-Pad36)") (class "Default")
      (node (ref "IC2") (pin "36") (pinfunction "NC_3_36") (pintype "passive+no_connect"))
    )
    (net (code "56") (name "unconnected-(IC2-NC_4-Pad44)") (class "Default")
      (node (ref "IC2") (pin "44") (pinfunction "NC_4_44") (pintype "passive+no_connect"))
    )
    (net (code "57") (name "unconnected-(IC2-NC_5-Pad45)") (class "Default")
      (node (ref "IC2") (pin "45") (pinfunction "NC_5_45") (pintype "passive+no_connect"))
    )
    (net (code "58") (name "unconnected-(IC2-NC_6-Pad47)") (class "Default")
      (node (ref "IC2") (pin "47") (pinfunction "NC_6_47") (pintype "passive+no_connect"))
    )
    (net (code "59") (name "unconnected-(IC2-NC_7-Pad48)") (class "Default")
      (node (ref "IC2") (pin "48") (pinfunction "NC_7_48") (pintype "passive+no_connect"))
    )
    (net (code "60") (name "unconnected-(IC2-SD0{slash}IO7-Pad32)") (class "Default")
      (node (ref "IC2") (pin "32") (pinfunction "SD0/IO7_32") (pintype "passive+no_connect"))
    )
    (net (code "61") (name "unconnected-(IC2-SD1{slash}IO8-Pad33)") (class "Default")
      (node (ref "IC2") (pin "33") (pinfunction "SD1/IO8_33") (pintype "passive+no_connect"))
    )
    (net (code "62") (name "unconnected-(IC2-SENSOR_CAPN{slash}I38-Pad7)") (class "Default")
      (node (ref "IC2") (pin "7") (pinfunction "SENSOR_CAPN/I38_7") (pintype "passive+no_connect"))
    )
    (net (code "63") (name "unconnected-(IC2-VDD_SDIO-Pad26)") (class "Default")
      (node (ref "IC2") (pin "26") (pinfunction "VDD_SDIO_26") (pintype "passive+no_connect"))
    )
    (net (code "64") (name "unconnected-(IC2-VDET_2{slash}I35-Pad11)") (class "Default")
      (node (ref "IC2") (pin "11") (pinfunction "VDET_2/I35_11") (pintype "passive+no_connect"))
    )
    (net (code "65") (name "unconnected-(IC3-DCC_SW-Pad14)") (class "Default")
      (node (ref "IC3") (pin "14") (pinfunction "DCC_SW_14") (pintype "passive+no_connect"))
    )
    (net (code "66") (name "unconnected-(IC3-DIO2-Pad9)") (class "Default")
      (node (ref "IC3") (pin "9") (pinfunction "DIO2_9") (pintype "passive+no_connect"))
    )
    (net (code "67") (name "unconnected-(IC3-DIO3-Pad10)") (class "Default")
      (node (ref "IC3") (pin "10") (pinfunction "DIO3_10") (pintype "passive+no_connect"))
    )
    (net (code "68") (name "unconnected-(IC4-DCC_SW-Pad14)") (class "Default")
      (node (ref "IC4") (pin "14") (pinfunction "DCC_SW_14") (pintype "passive+no_connect"))
    )
    (net (code "69") (name "unconnected-(IC4-DIO2-Pad9)") (class "Default")
      (node (ref "IC4") (pin "9") (pinfunction "DIO2_9") (pintype "passive+no_connect"))
    )
    (net (code "70") (name "unconnected-(IC4-DIO3-Pad10)") (class "Default")
      (node (ref "IC4") (pin "10") (pinfunction "DIO3_10") (pintype "passive+no_connect"))
    )
    (net (code "71") (name "unconnected-(IC5-DNC-Pad13)") (class "Default")
      (node (ref "IC5") (pin "13") (pinfunction "DNC_13") (pintype "passive+no_connect"))
    )
    (net (code "72") (name "unconnected-(IC6-DNC-Pad13)") (class "Default")
      (node (ref "IC6") (pin "13") (pinfunction "DNC_13") (pintype "passive+no_connect"))
    )
  )
)
